# Power_supply.net
KiCad netlist of a schematic drawn in Altium Designer
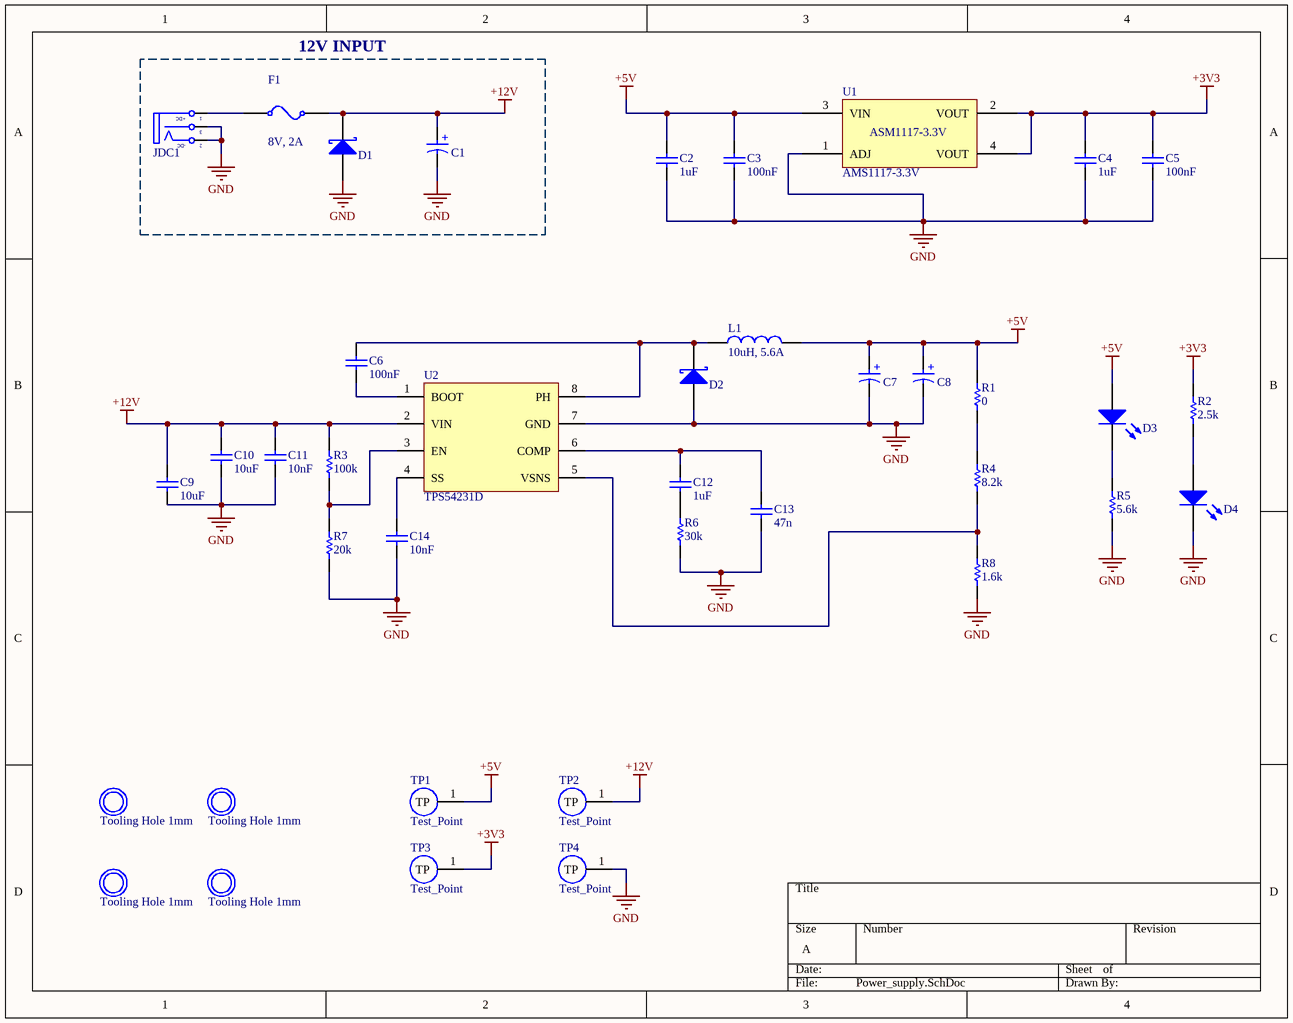
[diagram p0: Power_supply.SchDoc]

(export (version "E")
  (design (tool "Eeschema 10.0.6"))
  (components
    (comp (ref "C1")
      (value "47uF")
      (footprint "WCAP-ASLI_D4H5.5")
      (description "V-Chip, D4 x H5.5mm, 22uF, 16V")
      (libsource (lib "SMIOT_Lib_Schematic") (part "865080340003"))
    )
    (comp (ref "C2")
      (value "1uF")
      (footprint "CAP_0603")
      (description "CAP, size 0603, 1uF")
      (libsource (lib "SMIOT_Lib_Schematic") (part "01060310510"))
    )
    (comp (ref "C3")
      (value "100nF")
      (footprint "CAP_0603")
      (description "CAP, size 0603, 100nF")
      (libsource (lib "SMIOT_Lib_Schematic") (part "01060310410"))
    )
    (comp (ref "C4")
      (value "1uF")
      (footprint "CAP_0603")
      (description "CAP, size 0603, 1uF")
      (libsource (lib "SMIOT_Lib_Schematic") (part "01060310510"))
    )
    (comp (ref "C5")
      (value "100nF")
      (footprint "CAP_0603")
      (description "CAP, size 0603, 100nF")
      (libsource (lib "SMIOT_Lib_Schematic") (part "01060310410"))
    )
    (comp (ref "C6")
      (value "100nF")
      (footprint "CAP_0603")
      (description "CAP, size 0603, 100nF")
      (libsource (lib "SMIOT_Lib_Schematic") (part "01060310410"))
    )
    (comp (ref "C7")
      (value "47uF")
      (footprint "WCAP-ASLI_D5H5.5")
      (description "V-Chip, D5 x H5.5mm, 47uF, 16V")
      (libsource (lib "SMIOT_Lib_Schematic") (part "865080342006"))
    )
    (comp (ref "C8")
      (value "47uF")
      (footprint "WCAP-ASLI_D5H5.5")
      (description "V-Chip, D5 x H5.5mm, 47uF, 16V")
      (libsource (lib "SMIOT_Lib_Schematic") (part "865080342006"))
    )
    (comp (ref "C9")
      (value "10uF")
      (footprint "CAP_0603")
      (description "CAP, size 0603,10uF")
      (libsource (lib "SMIOT_Lib_Schematic") (part "01060310010"))
    )
    (comp (ref "C10")
      (value "10uF")
      (footprint "CAP_0603")
      (description "CAP, size 0603,10uF")
      (libsource (lib "SMIOT_Lib_Schematic") (part "01060310010"))
    )
    (comp (ref "C11")
      (value "10nF")
      (footprint "CAP_0603")
      (description "CAP, size 0603, 10nF")
      (libsource (lib "SMIOT_Lib_Schematic") (part "01060310310"))
    )
    (comp (ref "C12")
      (value "1uF")
      (footprint "CAP_0603")
      (description "CAP, size 0603, 1uF")
      (libsource (lib "SMIOT_Lib_Schematic") (part "01060310510"))
    )
    (comp (ref "C13")
      (value "47n")
      (footprint "CAP_0603")
      (description "CAP, size 0603, 47nF")
      (libsource (lib "SMIOT_Lib_Schematic") (part "01060347310"))
    )
    (comp (ref "C14")
      (value "10nF")
      (footprint "CAP_0603")
      (description "CAP, size 0603, 10nF")
      (libsource (lib "SMIOT_Lib_Schematic") (part "01060310310"))
    )
    (comp (ref "D1")
      (value "D Schottky")
      (footprint "SS34")
      (description "Schottky Diode")
      (fields (field (name "PUBLISHER") "Altium Limited"))
      (libsource (lib "Board_C24") (part "D Schottky"))
    )
    (comp (ref "D2")
      (value "D Schottky")
      (footprint "SS34")
      (description "Schottky Diode")
      (fields (field (name "PUBLISHER") "Altium Limited"))
      (libsource (lib "SMIOT_Lib_Schematic") (part "D Schottky"))
    )
    (comp (ref "D3")
      (value "LED SMD")
      (footprint "LED_0805_Blue")
      (description "LED")
      (libsource (lib "SMIOT_Lib_Schematic") (part "LED SMD"))
    )
    (comp (ref "D4")
      (value "LED SMD")
      (footprint "LED_0805_Blue")
      (description "LED")
      (libsource (lib "SMIOT_Lib_Schematic") (part "LED SMD"))
    )
    (comp (ref "F1")
      (value "8V, 2A")
      (footprint "Fuse_SMD_1812")
      (description "Resettable Fuse, Size 1812, 8V, 2A")
      (fields (field (name "MANUFACTURER") "Littelfuse"))
      (libsource (lib "SMIOT_Lib_Schematic") (part "061812200008"))
    )
    (comp (ref "H1")
      (value "Tooling Hole 1mm")
      (footprint "2mm")
      (libsource (lib "SMIOT_Lib_Schematic") (part "Tooling Hole 2mm"))
    )
    (comp (ref "H2")
      (value "Tooling Hole 1mm")
      (footprint "2mm")
      (libsource (lib "SMIOT_Lib_Schematic") (part "Tooling Hole 2mm"))
    )
    (comp (ref "H3")
      (value "Tooling Hole 1mm")
      (footprint "2mm")
      (libsource (lib "SMIOT_Lib_Schematic") (part "Tooling Hole 2mm"))
    )
    (comp (ref "H4")
      (value "Tooling Hole 1mm")
      (footprint "2mm")
      (libsource (lib "SMIOT_Lib_Schematic") (part "Tooling Hole 2mm"))
    )
    (comp (ref "JDC1")
      (value "Jack DC")
      (footprint "DC-IN")
      (description "Jack DC input")
      (libsource (lib "SMIOT_Lib_Schematic") (part "Jack DC"))
    )
    (comp (ref "L1")
      (value "10uH, 5.6A")
      (footprint "WE-PD2A_5848")
      (description "WE-PD2A SMT Power Inductor, size 5848, 10uH, 2.2A")
      (fields
        (field (name "MANUFACTURER PART NUMBER") "78477410")
        (field (name "MANUFACTURER") "Wurth Elektronik")
      )
      (libsource (lib "SMIOT_Lib_Schematic") (part "78477410"))
    )
    (comp (ref "R1")
      (value "0")
      (footprint "resistor_0603")
      (description "RES, 0 Ohm, size 0603, 1%")
      (libsource (lib "SMIOT_Lib_Schematic") (part "0006030001"))
    )
    (comp (ref "R2")
      (value "2.5k")
      (footprint "resistor_0603")
      (description "RES, 2.5K Ohm, size 0603, 5%")
      (libsource (lib "SMIOT_Lib_Schematic") (part "0006032525"))
    )
    (comp (ref "R3")
      (value "100k")
      (footprint "resistor_0603")
      (description "RES, 100k Ohm, size 0603, 1%")
      (libsource (lib "SMIOT_Lib_Schematic") (part "0006031041"))
    )
    (comp (ref "R4")
      (value "8.2k")
      (footprint "resistor_0603")
      (description "RES, 8.2 kOhms, size 0603, 1%")
      (libsource (lib "SMIOT_Lib_Schematic") (part "0006038251"))
    )
    (comp (ref "R5")
      (value "5.6k")
      (footprint "resistor_0603")
      (description "RES, 5.6k Ohm, size 0603, 1%")
      (libsource (lib "SMIOT_Lib_Schematic") (part "0006035621"))
    )
    (comp (ref "R6")
      (value "30k")
      (footprint "resistor_0603")
      (description "RES, 30k Ohm, size 0603, 1%")
      (libsource (lib "SMIOT_Lib_Schematic") (part "0006033205"))
    )
    (comp (ref "R7")
      (value "20k")
      (footprint "resistor_0603")
      (description "RES, 20 kOhms, size 0603, 1%")
      (libsource (lib "SMIOT_Lib_Schematic") (part "0006032031"))
    )
    (comp (ref "R8")
      (value "1.6k")
      (footprint "resistor_0603")
      (description "RES, 1.5 kOhms, size 0603, 1%")
      (libsource (lib "SMIOT_Lib_Schematic") (part "0006031521"))
    )
    (comp (ref "TP1")
      (value "Test_Point")
      (footprint "TP_2MM")
      (description "Test point, 2mm radius")
      (libsource (lib "SMIOT_Lib_Schematic") (part "Test_Point"))
    )
    (comp (ref "TP2")
      (value "Test_Point")
      (footprint "TP_2MM")
      (description "Test point, 2mm radius")
      (libsource (lib "SMIOT_Lib_Schematic") (part "Test_Point"))
    )
    (comp (ref "TP3")
      (value "Test_Point")
      (footprint "TP_2MM")
      (description "Test point, 2mm radius")
      (libsource (lib "SMIOT_Lib_Schematic") (part "Test_Point"))
    )
    (comp (ref "TP4")
      (value "Test_Point")
      (footprint "TP_2MM")
      (description "Test point, 2mm radius")
      (libsource (lib "SMIOT_Lib_Schematic") (part "Test_Point"))
    )
    (comp (ref "U1")
      (value "AMS1117-3.3V")
      (footprint "AMS1117-3.3V SOT223")
      (description "AMS1117-3.3V, OUT 3.3V 1A.")
      (fields (field (name "MANUFACTURER") "AMS"))
      (libsource (lib "SMIOT_Lib_Schematic") (part "AMS1117-3.3V"))
    )
    (comp (ref "U2")
      (value "TPS54231D")
      (footprint "SOIC8")
      (description "Buck Switching Regulator IC Positive Adjustable 0.8V 1 Output 2A 8-SOIC (0.154\", 3.90mm Width)")
      (fields (field (name "MFR") "Texas Instruments"))
      (libsource (lib "SMIOT_Lib_Schematic") (part "TPS54231"))
    )
  )
  (nets
    (net (code "1") (name "+3V3") (class "Default")
      (node (ref "C4") (pin "2") (pinfunction "2_2") (pintype "passive"))
      (node (ref "C5") (pin "2") (pinfunction "2_2") (pintype "passive"))
      (node (ref "R2") (pin "2") (pinfunction "2_2") (pintype "passive"))
      (node (ref "TP3") (pin "1") (pinfunction "TP_1") (pintype "passive"))
      (node (ref "U1") (pin "2") (pinfunction "VOUT_2") (pintype "passive"))
      (node (ref "U1") (pin "4") (pinfunction "VOUT_4") (pintype "power_in"))
    )
    (net (code "2") (name "+5V") (class "Default")
      (node (ref "C2") (pin "2") (pinfunction "2_2") (pintype "passive"))
      (node (ref "C3") (pin "2") (pinfunction "2_2") (pintype "passive"))
      (node (ref "C7") (pin "1") (pinfunction "P_1") (pintype "passive"))
      (node (ref "C8") (pin "1") (pinfunction "P_1") (pintype "passive"))
      (node (ref "D3") (pin "1") (pinfunction "A_1") (pintype "passive"))
      (node (ref "L1") (pin "2") (pinfunction "2_2") (pintype "passive"))
      (node (ref "R1") (pin "2") (pinfunction "2_2") (pintype "passive"))
      (node (ref "TP1") (pin "1") (pinfunction "TP_1") (pintype "passive"))
      (node (ref "U1") (pin "3") (pinfunction "VIN_3") (pintype "passive"))
    )
    (net (code "3") (name "+12V") (class "Default")
      (node (ref "C1") (pin "1") (pinfunction "P_1") (pintype "passive"))
      (node (ref "C10") (pin "2") (pinfunction "2_2") (pintype "passive"))
      (node (ref "C11") (pin "2") (pinfunction "2_2") (pintype "passive"))
      (node (ref "C9") (pin "2") (pinfunction "2_2") (pintype "passive"))
      (node (ref "D1") (pin "2") (pinfunction "K_2") (pintype "passive"))
      (node (ref "F1") (pin "1") (pinfunction "1_1") (pintype "passive"))
      (node (ref "R3") (pin "2") (pinfunction "2_2") (pintype "passive"))
      (node (ref "TP2") (pin "1") (pinfunction "TP_1") (pintype "passive"))
      (node (ref "U2") (pin "2") (pinfunction "VIN_2") (pintype "passive"))
    )
    (net (code "4") (name "GND") (class "Default")
      (node (ref "C1") (pin "2") (pinfunction "N_2") (pintype "passive"))
      (node (ref "C10") (pin "1") (pinfunction "1_1") (pintype "passive"))
      (node (ref "C11") (pin "1") (pinfunction "1_1") (pintype "passive"))
      (node (ref "C13") (pin "1") (pinfunction "1_1") (pintype "passive"))
      (node (ref "C14") (pin "1") (pinfunction "1_1") (pintype "passive"))
      (node (ref "C2") (pin "1") (pinfunction "1_1") (pintype "passive"))
      (node (ref "C3") (pin "1") (pinfunction "1_1") (pintype "passive"))
      (node (ref "C4") (pin "1") (pinfunction "1_1") (pintype "passive"))
      (node (ref "C5") (pin "1") (pinfunction "1_1") (pintype "passive"))
      (node (ref "C7") (pin "2") (pinfunction "N_2") (pintype "passive"))
      (node (ref "C8") (pin "2") (pinfunction "N_2") (pintype "passive"))
      (node (ref "C9") (pin "1") (pinfunction "1_1") (pintype "passive"))
      (node (ref "D1") (pin "1") (pinfunction "A_1") (pintype "passive"))
      (node (ref "D2") (pin "1") (pinfunction "A_1") (pintype "passive"))
      (node (ref "D4") (pin "2") (pinfunction "K_2") (pintype "passive"))
      (node (ref "JDC1") (pin "2") (pinfunction "TN_2") (pintype "passive"))
      (node (ref "JDC1") (pin "3") (pinfunction "S_3") (pintype "power_in"))
      (node (ref "R5") (pin "1") (pinfunction "1_1") (pintype "passive"))
      (node (ref "R6") (pin "1") (pinfunction "1_1") (pintype "passive"))
      (node (ref "R7") (pin "1") (pinfunction "1_1") (pintype "passive"))
      (node (ref "R8") (pin "1") (pinfunction "1_1") (pintype "passive"))
      (node (ref "TP4") (pin "1") (pinfunction "TP_1") (pintype "passive"))
      (node (ref "U1") (pin "1") (pinfunction "ADJ_1") (pintype "power_in"))
      (node (ref "U2") (pin "7") (pinfunction "GND_7") (pintype "passive"))
    )
    (net (code "5") (name "Net-(C12-Pad2)") (class "Default")
      (node (ref "C12") (pin "2") (pinfunction "2_2") (pintype "passive"))
      (node (ref "R6") (pin "2") (pinfunction "2_2") (pintype "passive"))
    )
    (net (code "6") (name "Net-(D2-K)") (class "Default")
      (node (ref "C6") (pin "2") (pinfunction "2_2") (pintype "passive"))
      (node (ref "D2") (pin "2") (pinfunction "K_2") (pintype "passive"))
      (node (ref "L1") (pin "1") (pinfunction "1_1") (pintype "passive"))
      (node (ref "U2") (pin "8") (pinfunction "PH_8") (pintype "passive"))
    )
    (net (code "7") (name "Net-(D3-K)") (class "Default")
      (node (ref "D3") (pin "2") (pinfunction "K_2") (pintype "passive"))
      (node (ref "R5") (pin "2") (pinfunction "2_2") (pintype "passive"))
    )
    (net (code "8") (name "Net-(D4-A)") (class "Default")
      (node (ref "D4") (pin "1") (pinfunction "A_1") (pintype "passive"))
      (node (ref "R2") (pin "1") (pinfunction "1_1") (pintype "passive"))
    )
    (net (code "9") (name "Net-(JDC1-T)") (class "Default")
      (node (ref "F1") (pin "0") (pinfunction "0_0") (pintype "passive"))
      (node (ref "JDC1") (pin "1") (pinfunction "T_1") (pintype "passive"))
    )
    (net (code "10") (name "Net-(R1-Pad1)") (class "Default")
      (node (ref "R1") (pin "1") (pinfunction "1_1") (pintype "passive"))
      (node (ref "R4") (pin "2") (pinfunction "2_2") (pintype "passive"))
    )
    (net (code "11") (name "Net-(U2-BOOT)") (class "Default")
      (node (ref "C6") (pin "1") (pinfunction "1_1") (pintype "passive"))
      (node (ref "U2") (pin "1") (pinfunction "BOOT_1") (pintype "passive"))
    )
    (net (code "12") (name "Net-(U2-COMP)") (class "Default")
      (node (ref "C12") (pin "1") (pinfunction "1_1") (pintype "passive"))
      (node (ref "C13") (pin "2") (pinfunction "2_2") (pintype "passive"))
      (node (ref "U2") (pin "6") (pinfunction "COMP_6") (pintype "passive"))
    )
    (net (code "13") (name "Net-(U2-EN)") (class "Default")
      (node (ref "R3") (pin "1") (pinfunction "1_1") (pintype "passive"))
      (node (ref "R7") (pin "2") (pinfunction "2_2") (pintype "passive"))
      (node (ref "U2") (pin "3") (pinfunction "EN_3") (pintype "passive"))
    )
    (net (code "14") (name "Net-(U2-SS)") (class "Default")
      (node (ref "C14") (pin "2") (pinfunction "2_2") (pintype "passive"))
      (node (ref "U2") (pin "4") (pinfunction "SS_4") (pintype "passive"))
    )
    (net (code "15") (name "Net-(U2-VSNS)") (class "Default")
      (node (ref "R4") (pin "1") (pinfunction "1_1") (pintype "passive"))
      (node (ref "R8") (pin "2") (pinfunction "2_2") (pintype "passive"))
      (node (ref "U2") (pin "5") (pinfunction "VSNS_5") (pintype "passive"))
    )
  )
)
